# PWM_Philter.net
KiCad netlist of a schematic drawn in Altium Designer
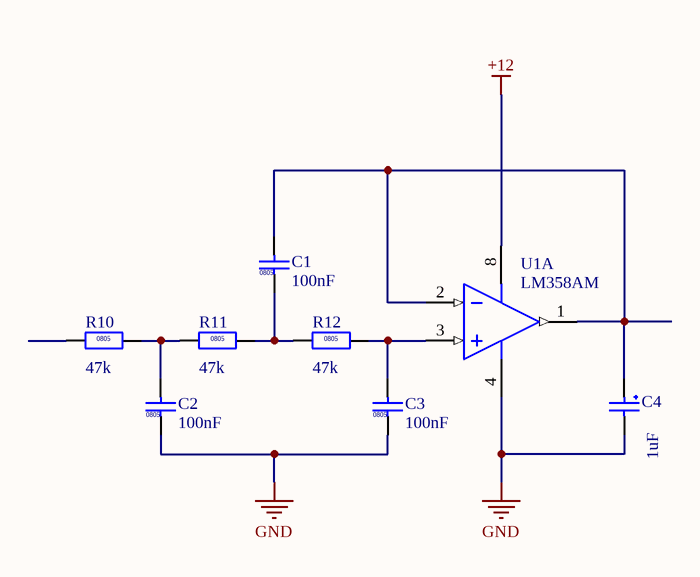
[diagram p0: PWM_Philter.SchDoc]

(export (version "E")
  (design (tool "Eeschema 10.0.6"))
  (components
    (comp (ref "C1")
      (value "100nF")
      (footprint "CAPC2012-0805M")
      (description "Capacitor 0805")
      (fields (field (name "Comment") "CAPC_0805"))
      (libsource (lib "Passive") (part "CAPC_0805"))
    )
    (comp (ref "C2")
      (value "100nF")
      (footprint "CAPC2012-0805M")
      (description "Capacitor 0805")
      (fields (field (name "Comment") "CAPC_0805"))
      (libsource (lib "Passive") (part "CAPC_0805"))
    )
    (comp (ref "C3")
      (value "100nF")
      (footprint "CAPC2012-0805M")
      (description "Capacitor 0805")
      (fields (field (name "Comment") "CAPC_0805"))
      (libsource (lib "Passive") (part "CAPC_0805"))
    )
    (comp (ref "C4")
      (value "1uF")
      (footprint "ECAP511")
      (description "Capacitor electrolytic 2.5 mm pitch, 5*11 body")
      (fields (field (name "Comment") "ECAP-511"))
      (libsource (lib "Passive") (part "ECAP-511"))
    )
    (comp (ref "R10")
      (value "47k")
      (footprint "RESC2012-0805M")
      (description "Resistor 0805")
      (fields (field (name "Comment") "RESC_0805_R"))
      (libsource (lib "Passive") (part "RESC_0805_R"))
    )
    (comp (ref "R11")
      (value "47k")
      (footprint "RESC2012-0805M")
      (description "Resistor 0805")
      (fields (field (name "Comment") "RESC_0805_R"))
      (libsource (lib "Passive") (part "RESC_0805_R"))
    )
    (comp (ref "R12")
      (value "47k")
      (footprint "RESC2012-0805M")
      (description "Resistor 0805")
      (fields (field (name "Comment") "RESC_0805_R"))
      (libsource (lib "Passive") (part "RESC_0805_R"))
    )
    (comp (ref "U1")
      (value "LM358AM")
      (footprint "SO-8_L")
      (description "Low Power Dual Operational Amplifier")
      (fields
        (field (name "MANUFACTURER") "National Semiconductor")
        (field (name "DIGIKEYPARTNUMBER") "LM358AMXCT-ND")
        (field (name "PUBLISHER") "Altium Limited")
      )
      (libsource (lib "Analog_IC") (part "LM358AM"))
    )
  )
  (nets
    (net (code "1") (name "+12") (class "Default")
      (node (ref "U1") (pin "8") (pinfunction "V+_8") (pintype "power_in"))
    )
    (net (code "2") (name "GND") (class "Default")
      (node (ref "C2") (pin "1") (pinfunction "1_1") (pintype "passive"))
      (node (ref "C3") (pin "1") (pinfunction "1_1") (pintype "passive"))
      (node (ref "C4") (pin "2") (pinfunction "2_2") (pintype "passive"))
      (node (ref "U1") (pin "4") (pinfunction "GND_4") (pintype "power_in"))
    )
    (net (code "3") (name "Net-(C1-Pad1)") (class "Default")
      (node (ref "C1") (pin "1") (pinfunction "1_1") (pintype "passive"))
      (node (ref "R11") (pin "2") (pinfunction "2_2") (pintype "passive"))
      (node (ref "R12") (pin "1") (pinfunction "1_1") (pintype "passive"))
    )
    (net (code "4") (name "Net-(C2-Pad2)") (class "Default")
      (node (ref "C2") (pin "2") (pinfunction "2_2") (pintype "passive"))
      (node (ref "R10") (pin "2") (pinfunction "2_2") (pintype "passive"))
      (node (ref "R11") (pin "1") (pinfunction "1_1") (pintype "passive"))
    )
    (net (code "5") (name "Net-(U1A-INA+)") (class "Default")
      (node (ref "C3") (pin "2") (pinfunction "2_2") (pintype "passive"))
      (node (ref "R12") (pin "2") (pinfunction "2_2") (pintype "passive"))
      (node (ref "U1") (pin "3") (pinfunction "INA+_3") (pintype "input"))
    )
    (net (code "6") (name "Net-(U1A-INA-)") (class "Default")
      (node (ref "C1") (pin "2") (pinfunction "2_2") (pintype "passive"))
      (node (ref "C4") (pin "1") (pinfunction "1_1") (pintype "passive"))
      (node (ref "U1") (pin "1") (pinfunction "OUTA_1") (pintype "output"))
      (node (ref "U1") (pin "2") (pinfunction "INA-_2") (pintype "input"))
    )
    (net (code "7") (name "unconnected-(R10-Pad1)") (class "Default")
      (node (ref "R10") (pin "1") (pinfunction "1_1") (pintype "passive"))
    )
  )
)
